# design.net
KiCad netlist of a schematic drawn in Altium Designer
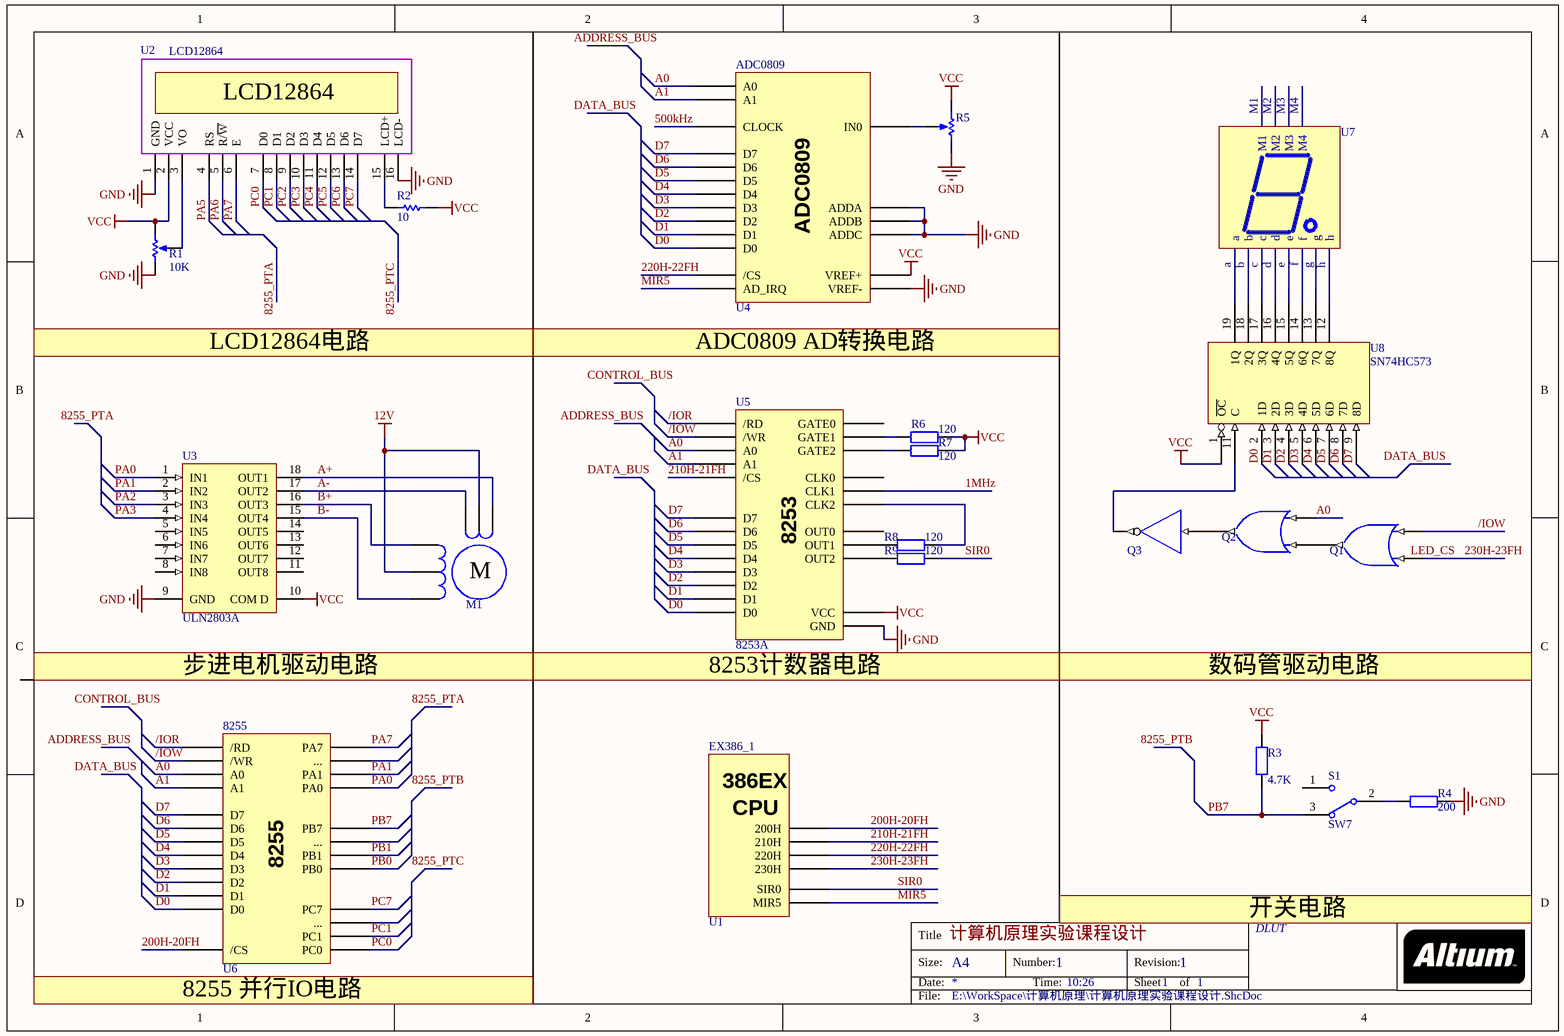
[diagram p0: 计算机原理课程设计.SchDoc]

(export (version "E")
  (design (tool "Eeschema 10.0.6"))
  (components
    (comp (ref "8255") (value "U6") (libsource (lib "计算机原理实验4") (part "8255")))
    (comp (ref "ADC0809") (value "U4") (libsource (lib "计算机原理实验5") (part "ADC0809")))
    (comp (ref "EX386_1") (value "U1") (libsource (lib "计算机原理实验4") (part "386EX")))
    (comp (ref "M1") (value "MOTOR STEPPER") (libsource (lib "Miscellaneous Devices") (part "MOTOR STEPPER")))
    (comp (ref "Q1") (value "OR") (description "OR Gate") (libsource (lib "Integrated_Library1") (part "OR")))
    (comp (ref "Q2") (value "OR") (description "OR Gate") (libsource (lib "Integrated_Library1") (part "OR")))
    (comp (ref "Q3")
      (value "NOT")
      (description "Inverter")
      (libsource (lib "Miscellaneous Devices") (part "NOT"))
    )
    (comp (ref "R1")
      (value "10K")
      (footprint "VR5")
      (description "Potentiometer")
      (fields (field (name "Comment") "RPot") (field (name "PUBLISHER") "Altium Limited"))
      (libsource (lib "Miscellaneous Devices") (part "RPot"))
    )
    (comp (ref "R2")
      (value "10")
      (footprint "AXIAL-0.3")
      (description "Resistor")
      (fields (field (name "Comment") "Res1") (field (name "PUBLISHER") "Altium Limited"))
      (libsource (lib "Miscellaneous Devices") (part "Res1"))
    )
    (comp (ref "R3")
      (value "4.7K")
      (footprint "AXIAL-0.4")
      (description "Resistor")
      (fields (field (name "Comment") "Res2") (field (name "PUBLISHER") "Altium Limited"))
      (libsource (lib "") (part "Res2_2"))
    )
    (comp (ref "R4")
      (value "200")
      (footprint "AXIAL-0.4")
      (description "Resistor")
      (fields (field (name "Comment") "Res2") (field (name "PUBLISHER") "Altium Limited"))
      (libsource (lib "") (part "Res2_1"))
    )
    (comp (ref "R5")
      (value "RPot")
      (footprint "VR5")
      (description "Potentiometer")
      (fields (field (name "PUBLISHER") "Altium Limited"))
      (libsource (lib "Miscellaneous Devices") (part "RPot"))
    )
    (comp (ref "R6")
      (value "120")
      (footprint "AXIAL-0.4")
      (description "Resistor")
      (fields (field (name "Comment") "Res2") (field (name "PUBLISHER") "Altium Limited"))
      (libsource (lib "Miscellaneous Devices") (part "Res2"))
    )
    (comp (ref "R7")
      (value "120")
      (footprint "AXIAL-0.4")
      (description "Resistor")
      (fields (field (name "Comment") "Res2") (field (name "PUBLISHER") "Altium Limited"))
      (libsource (lib "Miscellaneous Devices") (part "Res2"))
    )
    (comp (ref "R8")
      (value "120")
      (footprint "AXIAL-0.4")
      (description "Resistor")
      (fields (field (name "Comment") "Res2") (field (name "PUBLISHER") "Altium Limited"))
      (libsource (lib "Miscellaneous Devices") (part "Res2"))
    )
    (comp (ref "R9")
      (value "120")
      (footprint "AXIAL-0.4")
      (description "Resistor")
      (fields (field (name "Comment") "Res2") (field (name "PUBLISHER") "Altium Limited"))
      (libsource (lib "Miscellaneous Devices") (part "Res2"))
    )
    (comp (ref "S1")
      (value "SW7")
      (footprint "TL36WW15050")
      (description "SPDT Subminiature Toggle Switch, Right Angle Mounting, Vertical Actuation")
      (fields (field (name "PUBLISHER") "Altium Limited"))
      (libsource (lib "Miscellaneous Devices") (part "SW-SPDT"))
    )
    (comp (ref "U2")
      (value "LCD12864")
      (footprint "LCD1602")
      (libsource (lib "My Footprint") (part "LCD1602"))
    )
    (comp (ref "U3")
      (value "ULN2803A")
      (footprint "A18")
      (description "High-Voltage, High-Current Darlington Array")
      (fields (field (name "PUBLISHER") "Altium Limited"))
      (libsource (lib "Allegro Interface Darlington Driver") (part "ULN2803A"))
    )
    (comp (ref "U5") (value "8253A") (libsource (lib "计算机原理实验4") (part "8253A")))
    (comp (ref "U7")
      (value "4_8SEG_LED")
      (footprint "4-8SLED(B)")
      (libsource (lib "声亮元件") (part "4_8SEG_LED"))
    )
    (comp (ref "U8")
      (value "SN74HC573")
      (footprint "DIP-20")
      (description "OCTAL D-TYPE TRANSPARENT LCH 3SO")
      (libsource (lib "CMOS&TTL74") (part "SN74HC573"))
    )
  )
  (nets
    (net (code "1") (name "/1MHz") (class "Default")
      (node (ref "U5") (pin "GND") (pinfunction "CLK1_GND") (pintype "passive"))
    )
    (net (code "2") (name "/200H-20FH") (class "Default")
      (node (ref "8255") (pin "GND") (pinfunction "/CS_GND") (pintype "passive"))
      (node (ref "EX386_1") (pin "GND") (pinfunction "200H_GND") (pintype "passive"))
    )
    (net (code "3") (name "/210H-21FH") (class "Default")
      (node (ref "EX386_1") (pin "GND") (pinfunction "210H_GND") (pintype "passive"))
      (node (ref "U5") (pin "GND") (pinfunction "/CS_GND") (pintype "passive"))
    )
    (net (code "4") (name "/220H-22FH") (class "Default")
      (node (ref "ADC0809") (pin "GND") (pinfunction "/CS_GND") (pintype "passive"))
      (node (ref "EX386_1") (pin "GND") (pinfunction "220H_GND") (pintype "passive"))
    )
    (net (code "5") (name "/230H-23FH") (class "Default")
      (node (ref "EX386_1") (pin "GND") (pinfunction "230H_GND") (pintype "passive"))
      (node (ref "Q1") (pin "1") (pinfunction "A_1") (pintype "input"))
    )
    (net (code "6") (name "/500kHz") (class "Default")
      (node (ref "ADC0809") (pin "GND") (pinfunction "CLOCK_GND") (pintype "passive"))
    )
    (net (code "10") (name "/A+") (class "Default")
      (node (ref "M1") (pin "1") (pinfunction "1_1") (pintype "passive"))
      (node (ref "U3") (pin "18") (pinfunction "OUT1_18") (pintype "open_collector"))
    )
    (net (code "11") (name "/A-") (class "Default")
      (node (ref "M1") (pin "3") (pinfunction "3_3") (pintype "passive"))
      (node (ref "U3") (pin "17") (pinfunction "OUT2_17") (pintype "open_collector"))
    )
    (net (code "12") (name "/A0") (class "Default")
      (node (ref "8255") (pin "GND") (pinfunction "A0_GND") (pintype "passive"))
      (node (ref "ADC0809") (pin "GND") (pinfunction "A0_GND") (pintype "passive"))
      (node (ref "Q2") (pin "2") (pinfunction "B_2") (pintype "input"))
      (node (ref "U5") (pin "GND") (pinfunction "A0_GND") (pintype "passive"))
    )
    (net (code "13") (name "/A1") (class "Default")
      (node (ref "8255") (pin "GND") (pinfunction "A1_GND") (pintype "passive"))
      (node (ref "ADC0809") (pin "GND") (pinfunction "A1_GND") (pintype "passive"))
      (node (ref "U5") (pin "GND") (pinfunction "A1_GND") (pintype "passive"))
    )
    (net (code "15") (name "/B+") (class "Default")
      (node (ref "M1") (pin "4") (pinfunction "4_4") (pintype "passive"))
      (node (ref "U3") (pin "16") (pinfunction "OUT3_16") (pintype "open_collector"))
    )
    (net (code "16") (name "/B-") (class "Default")
      (node (ref "M1") (pin "6") (pinfunction "6_6") (pintype "passive"))
      (node (ref "U3") (pin "15") (pinfunction "OUT4_15") (pintype "open_collector"))
    )
    (net (code "18") (name "/D0") (class "Default")
      (node (ref "8255") (pin "GND") (pinfunction "D0_GND") (pintype "passive"))
      (node (ref "ADC0809") (pin "GND") (pinfunction "D0_GND") (pintype "passive"))
      (node (ref "U5") (pin "GND") (pinfunction "D0_GND") (pintype "passive"))
      (node (ref "U8") (pin "2") (pinfunction "1D_2") (pintype "input"))
    )
    (net (code "19") (name "/D1") (class "Default")
      (node (ref "8255") (pin "GND") (pinfunction "D1_GND") (pintype "passive"))
      (node (ref "ADC0809") (pin "GND") (pinfunction "D1_GND") (pintype "passive"))
      (node (ref "U5") (pin "GND") (pinfunction "D1_GND") (pintype "passive"))
      (node (ref "U8") (pin "3") (pinfunction "2D_3") (pintype "input"))
    )
    (net (code "20") (name "/D2") (class "Default")
      (node (ref "8255") (pin "GND") (pinfunction "D2_GND") (pintype "passive"))
      (node (ref "ADC0809") (pin "GND") (pinfunction "D2_GND") (pintype "passive"))
      (node (ref "U5") (pin "GND") (pinfunction "D2_GND") (pintype "passive"))
      (node (ref "U8") (pin "4") (pinfunction "3D_4") (pintype "input"))
    )
    (net (code "21") (name "/D3") (class "Default")
      (node (ref "8255") (pin "GND") (pinfunction "D3_GND") (pintype "passive"))
      (node (ref "ADC0809") (pin "GND") (pinfunction "D3_GND") (pintype "passive"))
      (node (ref "U5") (pin "GND") (pinfunction "D3_GND") (pintype "passive"))
      (node (ref "U8") (pin "5") (pinfunction "4D_5") (pintype "input"))
    )
    (net (code "22") (name "/D4") (class "Default")
      (node (ref "8255") (pin "GND") (pinfunction "D4_GND") (pintype "passive"))
      (node (ref "ADC0809") (pin "GND") (pinfunction "D4_GND") (pintype "passive"))
      (node (ref "U5") (pin "GND") (pinfunction "D4_GND") (pintype "passive"))
      (node (ref "U8") (pin "6") (pinfunction "5D_6") (pintype "input"))
    )
    (net (code "23") (name "/D5") (class "Default")
      (node (ref "8255") (pin "GND") (pinfunction "D5_GND") (pintype "passive"))
      (node (ref "ADC0809") (pin "GND") (pinfunction "D5_GND") (pintype "passive"))
      (node (ref "U5") (pin "GND") (pinfunction "D5_GND") (pintype "passive"))
      (node (ref "U8") (pin "7") (pinfunction "6D_7") (pintype "input"))
    )
    (net (code "24") (name "/D6") (class "Default")
      (node (ref "8255") (pin "GND") (pinfunction "D6_GND") (pintype "passive"))
      (node (ref "ADC0809") (pin "GND") (pinfunction "D6_GND") (pintype "passive"))
      (node (ref "U5") (pin "GND") (pinfunction "D6_GND") (pintype "passive"))
      (node (ref "U8") (pin "8") (pinfunction "7D_8") (pintype "input"))
    )
    (net (code "25") (name "/D7") (class "Default")
      (node (ref "8255") (pin "GND") (pinfunction "D7_GND") (pintype "passive"))
      (node (ref "ADC0809") (pin "GND") (pinfunction "D7_GND") (pintype "passive"))
      (node (ref "U5") (pin "GND") (pinfunction "D7_GND") (pintype "passive"))
      (node (ref "U8") (pin "9") (pinfunction "8D_9") (pintype "input"))
    )
    (net (code "27") (name "/MIR5") (class "Default")
      (node (ref "ADC0809") (pin "GND") (pinfunction "AD_IRQ_GND") (pintype "passive"))
      (node (ref "EX386_1") (pin "GND") (pinfunction "MIR5_GND") (pintype "passive"))
    )
    (net (code "28") (name "/PA0") (class "Default")
      (node (ref "8255") (pin "GND") (pinfunction "PA0_GND") (pintype "passive"))
      (node (ref "U3") (pin "1") (pinfunction "IN1_1") (pintype "input"))
    )
    (net (code "29") (name "/PA1") (class "Default")
      (node (ref "8255") (pin "GND") (pinfunction "PA1_GND") (pintype "passive"))
      (node (ref "U3") (pin "2") (pinfunction "IN2_2") (pintype "input"))
    )
    (net (code "30") (name "/PA2") (class "Default")
      (node (ref "U3") (pin "3") (pinfunction "IN3_3") (pintype "input"))
    )
    (net (code "31") (name "/PA3") (class "Default")
      (node (ref "U3") (pin "4") (pinfunction "IN4_4") (pintype "input"))
    )
    (net (code "32") (name "/PA5") (class "Default")
      (node (ref "U2") (pin "4") (pinfunction "RS_4") (pintype "passive"))
    )
    (net (code "33") (name "/PA6") (class "Default")
      (node (ref "U2") (pin "5") (pinfunction "R/~{W}_5") (pintype "passive"))
    )
    (net (code "34") (name "/PA7") (class "Default")
      (node (ref "8255") (pin "GND") (pinfunction "PA7_GND") (pintype "passive"))
      (node (ref "U2") (pin "6") (pinfunction "E_6") (pintype "passive"))
    )
    (net (code "35") (name "/PB0") (class "Default")
      (node (ref "8255") (pin "GND") (pinfunction "PB0_GND") (pintype "passive"))
    )
    (net (code "36") (name "/PB1") (class "Default")
      (node (ref "8255") (pin "GND") (pinfunction "PB1_GND") (pintype "passive"))
    )
    (net (code "37") (name "/PB7") (class "Default")
      (node (ref "8255") (pin "GND") (pinfunction "PB7_GND") (pintype "passive"))
      (node (ref "R3") (pin "1") (pinfunction "1_1") (pintype "passive"))
      (node (ref "S1") (pin "3") (pinfunction "3_3") (pintype "passive"))
    )
    (net (code "38") (name "/PC0") (class "Default")
      (node (ref "8255") (pin "GND") (pinfunction "PC0_GND") (pintype "passive"))
      (node (ref "U2") (pin "7") (pinfunction "D0_7") (pintype "passive"))
    )
    (net (code "39") (name "/PC1") (class "Default")
      (node (ref "8255") (pin "GND") (pinfunction "PC1_GND") (pintype "passive"))
      (node (ref "U2") (pin "8") (pinfunction "D1_8") (pintype "passive"))
    )
    (net (code "40") (name "/PC2") (class "Default")
      (node (ref "U2") (pin "9") (pinfunction "D2_9") (pintype "passive"))
    )
    (net (code "41") (name "/PC3") (class "Default")
      (node (ref "U2") (pin "10") (pinfunction "D3_10") (pintype "passive"))
    )
    (net (code "42") (name "/PC4") (class "Default")
      (node (ref "U2") (pin "11") (pinfunction "D4_11") (pintype "passive"))
    )
    (net (code "43") (name "/PC5") (class "Default")
      (node (ref "U2") (pin "12") (pinfunction "D5_12") (pintype "passive"))
    )
    (net (code "44") (name "/PC6") (class "Default")
      (node (ref "U2") (pin "13") (pinfunction "D6_13") (pintype "passive"))
    )
    (net (code "45") (name "/PC7") (class "Default")
      (node (ref "8255") (pin "GND") (pinfunction "PC7_GND") (pintype "passive"))
      (node (ref "U2") (pin "14") (pinfunction "D7_14") (pintype "passive"))
    )
    (net (code "46") (name "/SIR0") (class "Default")
      (node (ref "EX386_1") (pin "GND") (pinfunction "SIR0_GND") (pintype "passive"))
      (node (ref "R9") (pin "2") (pinfunction "2_2") (pintype "passive"))
    )
    (net (code "47") (name "/{slash}IOR") (class "Default")
      (node (ref "8255") (pin "GND") (pinfunction "/RD_GND") (pintype "passive"))
      (node (ref "U5") (pin "GND") (pinfunction "/RD_GND") (pintype "passive"))
    )
    (net (code "48") (name "/{slash}IOW") (class "Default")
      (node (ref "8255") (pin "GND") (pinfunction "/WR_GND") (pintype "passive"))
      (node (ref "Q1") (pin "2") (pinfunction "B_2") (pintype "input"))
      (node (ref "U5") (pin "GND") (pinfunction "/WR_GND") (pintype "passive"))
    )
    (net (code "49") (name "12V") (class "Default")
      (node (ref "M1") (pin "2") (pinfunction "2_2") (pintype "passive"))
      (node (ref "M1") (pin "5") (pinfunction "5_5") (pintype "passive"))
    )
    (net (code "50") (name "GND") (class "Default")
      (node (ref "ADC0809") (pin "GND") (pinfunction "VREF-_GND") (pintype "passive"))
      (node (ref "R1") (pin "1") (pinfunction "TOP_1") (pintype "passive"))
      (node (ref "R4") (pin "1") (pinfunction "1_1") (pintype "passive"))
      (node (ref "R5") (pin "2") (pinfunction "BOT_2") (pintype "passive"))
      (node (ref "U2") (pin "1") (pinfunction "GND_1") (pintype "passive"))
      (node (ref "U2") (pin "16") (pinfunction "LCD-_16") (pintype "passive"))
      (node (ref "U3") (pin "9") (pinfunction "GND_9") (pintype "power_in"))
      (node (ref "U5") (pin "GND") (pinfunction "GND_GND") (pintype "passive"))
      (node (ref "U8") (pin "10") (pinfunction "GND_10") (pintype "power_in"))
    )
    (net (code "51") (name "Net-(ADC0809-IN0)") (class "Default")
      (node (ref "ADC0809") (pin "GND") (pinfunction "IN0_GND") (pintype "passive"))
      (node (ref "R5") (pin "3") (pinfunction "TAP_3") (pintype "passive"))
    )
    (net (code "52") (name "Net-(Q1-Y)") (class "Default")
      (node (ref "Q1") (pin "3") (pinfunction "Y_3") (pintype "output"))
      (node (ref "Q2") (pin "1") (pinfunction "A_1") (pintype "input"))
    )
    (net (code "53") (name "Net-(Q2-Y)") (class "Default")
      (node (ref "Q2") (pin "3") (pinfunction "Y_3") (pintype "output"))
      (node (ref "Q3") (pin "1") (pinfunction "A_1") (pintype "input"))
    )
    (net (code "54") (name "Net-(Q3-Y)") (class "Default")
      (node (ref "Q3") (pin "2") (pinfunction "Y_2") (pintype "output"))
      (node (ref "U8") (pin "11") (pinfunction "C_11") (pintype "input"))
    )
    (net (code "55") (name "Net-(R1-TAP)") (class "Default")
      (node (ref "R1") (pin "3") (pinfunction "TAP_3") (pintype "passive"))
      (node (ref "U2") (pin "3") (pinfunction "VO_3") (pintype "passive"))
    )
    (net (code "56") (name "Net-(R4-Pad2)") (class "Default")
      (node (ref "R4") (pin "2") (pinfunction "2_2") (pintype "passive"))
      (node (ref "S1") (pin "2") (pinfunction "2_2") (pintype "passive"))
    )
    (net (code "57") (name "Net-(U2-LCD+)") (class "Default")
      (node (ref "R2") (pin "2") (pinfunction "2_2") (pintype "passive"))
      (node (ref "U2") (pin "15") (pinfunction "LCD+_15") (pintype "passive"))
    )
    (net (code "58") (name "Net-(U5-CLK2)") (class "Default")
      (node (ref "R8") (pin "2") (pinfunction "2_2") (pintype "passive"))
      (node (ref "U5") (pin "GND") (pinfunction "CLK2_GND") (pintype "passive"))
    )
    (net (code "59") (name "Net-(U5-GATE1)") (class "Default")
      (node (ref "R6") (pin "1") (pinfunction "1_1") (pintype "passive"))
      (node (ref "U5") (pin "GND") (pinfunction "GATE1_GND") (pintype "passive"))
    )
    (net (code "60") (name "Net-(U5-GATE2)") (class "Default")
      (node (ref "R7") (pin "1") (pinfunction "1_1") (pintype "passive"))
      (node (ref "U5") (pin "GND") (pinfunction "GATE2_GND") (pintype "passive"))
    )
    (net (code "61") (name "Net-(U5-OUT1)") (class "Default")
      (node (ref "R8") (pin "1") (pinfunction "1_1") (pintype "passive"))
      (node (ref "U5") (pin "GND") (pinfunction "OUT1_GND") (pintype "passive"))
    )
    (net (code "62") (name "Net-(U5-OUT2)") (class "Default")
      (node (ref "R9") (pin "1") (pinfunction "1_1") (pintype "passive"))
      (node (ref "U5") (pin "GND") (pinfunction "OUT2_GND") (pintype "passive"))
    )
    (net (code "63") (name "Net-(U8-1Q)") (class "Default")
      (node (ref "U7") (pin "a") (pinfunction "a_a") (pintype "passive"))
      (node (ref "U8") (pin "19") (pinfunction "1Q_19") (pintype "tri_state"))
    )
    (net (code "64") (name "Net-(U8-2Q)") (class "Default")
      (node (ref "U7") (pin "b") (pinfunction "b_b") (pintype "passive"))
      (node (ref "U8") (pin "18") (pinfunction "2Q_18") (pintype "tri_state"))
    )
    (net (code "65") (name "Net-(U8-3Q)") (class "Default")
      (node (ref "U7") (pin "c") (pinfunction "c_c") (pintype "passive"))
      (node (ref "U8") (pin "17") (pinfunction "3Q_17") (pintype "tri_state"))
    )
    (net (code "66") (name "Net-(U8-4Q)") (class "Default")
      (node (ref "U7") (pin "d") (pinfunction "d_d") (pintype "passive"))
      (node (ref "U8") (pin "16") (pinfunction "4Q_16") (pintype "tri_state"))
    )
    (net (code "67") (name "Net-(U8-5Q)") (class "Default")
      (node (ref "U7") (pin "e") (pinfunction "e_e") (pintype "passive"))
      (node (ref "U8") (pin "15") (pinfunction "5Q_15") (pintype "tri_state"))
    )
    (net (code "68") (name "Net-(U8-6Q)") (class "Default")
      (node (ref "U7") (pin "f") (pinfunction "f_f") (pintype "passive"))
      (node (ref "U8") (pin "14") (pinfunction "6Q_14") (pintype "tri_state"))
    )
    (net (code "69") (name "Net-(U8-7Q)") (class "Default")
      (node (ref "U7") (pin "g") (pinfunction "g_g") (pintype "passive"))
      (node (ref "U8") (pin "13") (pinfunction "7Q_13") (pintype "tri_state"))
    )
    (net (code "70") (name "Net-(U8-8Q)") (class "Default")
      (node (ref "U7") (pin "h") (pinfunction "h_h") (pintype "passive"))
      (node (ref "U8") (pin "12") (pinfunction "8Q_12") (pintype "tri_state"))
    )
    (net (code "71") (name "VCC") (class "Default")
      (node (ref "ADC0809") (pin "GND") (pinfunction "VREF+_GND") (pintype "passive"))
      (node (ref "R1") (pin "2") (pinfunction "BOT_2") (pintype "passive"))
      (node (ref "R2") (pin "1") (pinfunction "1_1") (pintype "passive"))
      (node (ref "R3") (pin "2") (pinfunction "2_2") (pintype "passive"))
      (node (ref "R5") (pin "1") (pinfunction "TOP_1") (pintype "passive"))
      (node (ref "R6") (pin "2") (pinfunction "2_2") (pintype "passive"))
      (node (ref "R7") (pin "2") (pinfunction "2_2") (pintype "passive"))
      (node (ref "U2") (pin "2") (pinfunction "VCC_2") (pintype "passive"))
      (node (ref "U3") (pin "10") (pinfunction "COM_D_10") (pintype "passive"))
      (node (ref "U5") (pin "GND") (pinfunction "VCC_GND") (pintype "passive"))
      (node (ref "U8") (pin "1") (pinfunction "~{OC}_1") (pintype "input"))
      (node (ref "U8") (pin "20") (pinfunction "VCC_20") (pintype "power_in"))
    )
    (net (code "72") (name "unconnected-(8255-...-PadGND)") (class "Default")
      (node (ref "8255") (pin "GND") (pinfunction "..._GND") (pintype "passive"))
    )
    (net (code "73") (name "unconnected-(8255-...-PadGND)_1") (class "Default")
      (node (ref "8255") (pin "GND") (pinfunction "..._GND") (pintype "passive"))
    )
    (net (code "74") (name "unconnected-(8255-...-PadGND)_2") (class "Default")
      (node (ref "8255") (pin "GND") (pinfunction "..._GND") (pintype "passive"))
    )
    (net (code "75") (name "unconnected-(S1-Pad1)") (class "Default")
      (node (ref "S1") (pin "1") (pinfunction "1_1") (pintype "passive"))
    )
    (net (code "76") (name "unconnected-(U3-IN5-Pad5)") (class "Default")
      (node (ref "U3") (pin "5") (pinfunction "IN5_5") (pintype "input"))
    )
    (net (code "77") (name "unconnected-(U3-IN6-Pad6)") (class "Default")
      (node (ref "U3") (pin "6") (pinfunction "IN6_6") (pintype "input"))
    )
    (net (code "78") (name "unconnected-(U3-IN7-Pad7)") (class "Default")
      (node (ref "U3") (pin "7") (pinfunction "IN7_7") (pintype "input"))
    )
    (net (code "79") (name "unconnected-(U3-IN8-Pad8)") (class "Default")
      (node (ref "U3") (pin "8") (pinfunction "IN8_8") (pintype "input"))
    )
    (net (code "80") (name "unconnected-(U3-OUT5-Pad14)") (class "Default")
      (node (ref "U3") (pin "14") (pinfunction "OUT5_14") (pintype "open_collector"))
    )
    (net (code "81") (name "unconnected-(U3-OUT6-Pad13)") (class "Default")
      (node (ref "U3") (pin "13") (pinfunction "OUT6_13") (pintype "open_collector"))
    )
    (net (code "82") (name "unconnected-(U3-OUT7-Pad12)") (class "Default")
      (node (ref "U3") (pin "12") (pinfunction "OUT7_12") (pintype "open_collector"))
    )
    (net (code "83") (name "unconnected-(U3-OUT8-Pad11)") (class "Default")
      (node (ref "U3") (pin "11") (pinfunction "OUT8_11") (pintype "open_collector"))
    )
    (net (code "84") (name "unconnected-(U5-CLK0-PadGND)") (class "Default")
      (node (ref "U5") (pin "GND") (pinfunction "CLK0_GND") (pintype "passive"))
    )
    (net (code "85") (name "unconnected-(U5-GATE0-PadGND)") (class "Default")
      (node (ref "U5") (pin "GND") (pinfunction "GATE0_GND") (pintype "passive"))
    )
    (net (code "86") (name "unconnected-(U5-OUT0-PadGND)") (class "Default")
      (node (ref "U5") (pin "GND") (pinfunction "OUT0_GND") (pintype "passive"))
    )
    (net (code "87") (name "unconnected-(U7-PadM1)") (class "Default")
      (node (ref "U7") (pin "M1") (pinfunction "M1_M1") (pintype "passive"))
    )
    (net (code "88") (name "unconnected-(U7-PadM2)") (class "Default")
      (node (ref "U7") (pin "M2") (pinfunction "M2_M2") (pintype "passive"))
    )
    (net (code "89") (name "unconnected-(U7-PadM3)") (class "Default")
      (node (ref "U7") (pin "M3") (pinfunction "M3_M3") (pintype "passive"))
    )
    (net (code "90") (name "unconnected-(U7-PadM4)") (class "Default")
      (node (ref "U7") (pin "M4") (pinfunction "M4_M4") (pintype "passive"))
    )
  )
)
